# Un_Usb.net
KiCad netlist of a schematic drawn in EAGLE
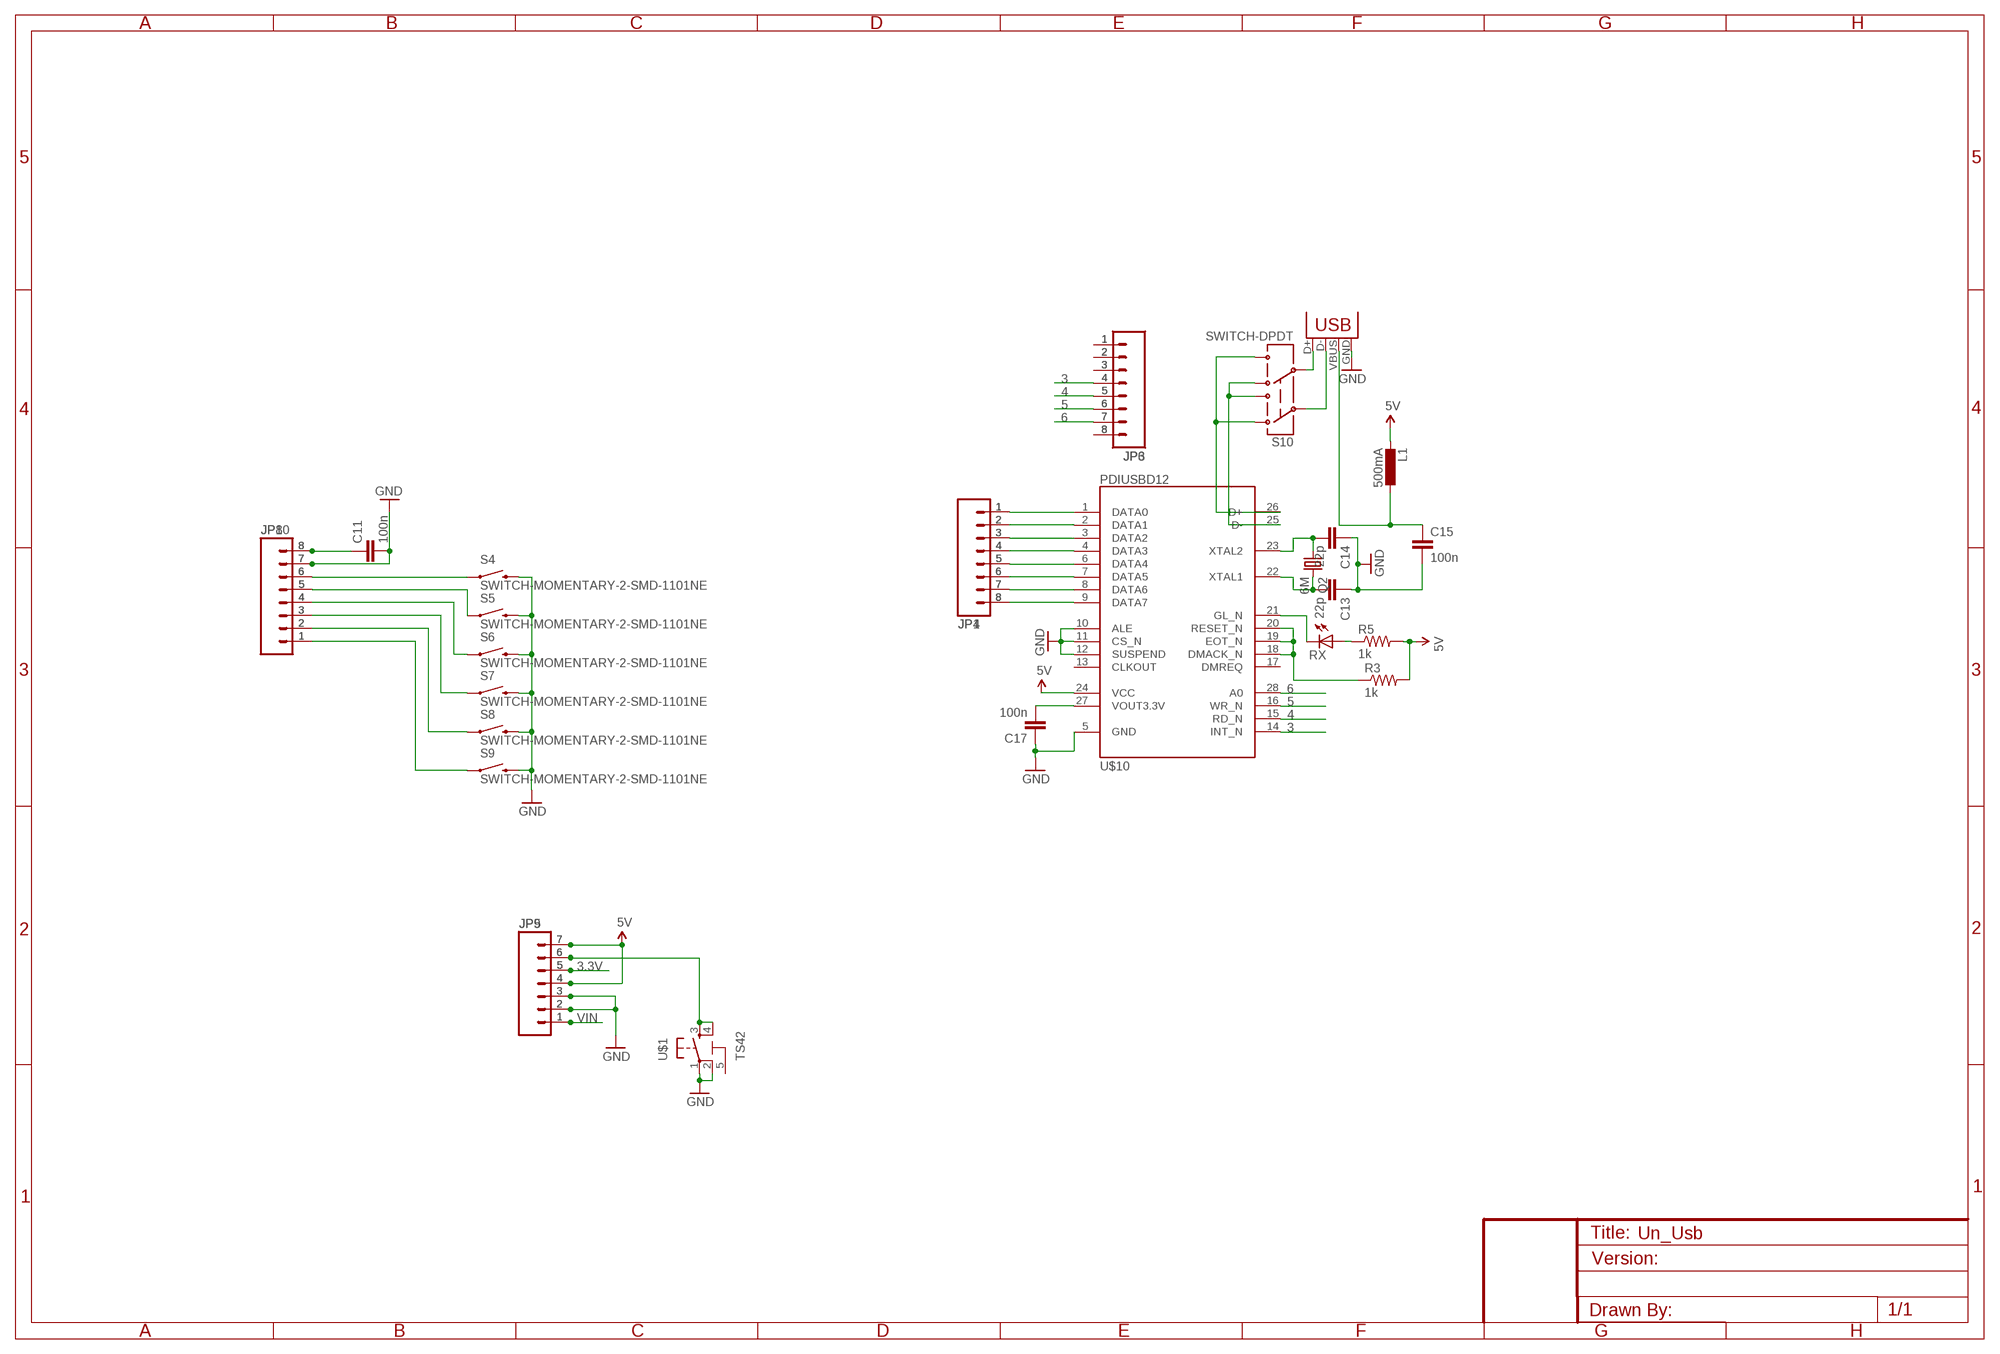
[diagram p0: schematic, sheet 1]

(export (version "E")
  (design (tool "Eeschema 10.0.6"))
  (components
    (comp (ref "C11")
      (value "100n")
      (footprint "eagle-import:0603-CAP")
      (libsource (lib "eagle-import") (part "CAP0603-CAP"))
    )
    (comp (ref "C13")
      (value "22p")
      (footprint "eagle-import:0805")
      (libsource (lib "eagle-import") (part "CAP0805"))
    )
    (comp (ref "C14")
      (value "22p")
      (footprint "eagle-import:0805")
      (libsource (lib "eagle-import") (part "CAP0805"))
    )
    (comp (ref "C15")
      (value "100n")
      (footprint "eagle-import:0603-CAP")
      (libsource (lib "eagle-import") (part "CAP0603-CAP"))
    )
    (comp (ref "C17")
      (value "100n")
      (footprint "eagle-import:0603-CAP")
      (libsource (lib "eagle-import") (part "CAP0603-CAP"))
    )
    (comp (ref "JP1")
      (value "M081X08")
      (footprint "eagle-import:1X08")
      (libsource (lib "eagle-import") (part "M081X08"))
    )
    (comp (ref "JP3")
      (value "M08")
      (footprint "eagle-import:1X08")
      (libsource (lib "eagle-import") (part "M08"))
    )
    (comp (ref "JP4")
      (value "M081X08")
      (footprint "eagle-import:1X08")
      (libsource (lib "eagle-import") (part "M081X08"))
    )
    (comp (ref "JP5")
      (value "M07")
      (footprint "eagle-import:1X07")
      (libsource (lib "eagle-import") (part "M07"))
    )
    (comp (ref "JP6")
      (value "M08")
      (footprint "eagle-import:1X08")
      (libsource (lib "eagle-import") (part "M08"))
    )
    (comp (ref "JP8")
      (value "M08")
      (footprint "eagle-import:1X08")
      (libsource (lib "eagle-import") (part "M08"))
    )
    (comp (ref "JP9")
      (value "M07")
      (footprint "eagle-import:1X07")
      (libsource (lib "eagle-import") (part "M07"))
    )
    (comp (ref "JP10")
      (value "M08")
      (footprint "eagle-import:1X08")
      (libsource (lib "eagle-import") (part "M08"))
    )
    (comp (ref "L1")
      (value "500mA")
      (footprint "eagle-import:L1812")
      (libsource (lib "eagle-import") (part "L-EUL1812"))
    )
    (comp (ref "Q2")
      (value "6M")
      (footprint "eagle-import:HC49US")
      (libsource (lib "eagle-import") (part "CRYSTALHC49US"))
    )
    (comp (ref "R3")
      (value "1k")
      (footprint "eagle-import:0805")
      (libsource (lib "eagle-import") (part "RESISTOR0805-RES"))
    )
    (comp (ref "R5")
      (value "1k")
      (footprint "eagle-import:0805")
      (libsource (lib "eagle-import") (part "RESISTOR0805-RES"))
    )
    (comp (ref "RX")
      (value "LED0805")
      (footprint "eagle-import:LED-0805")
      (libsource (lib "eagle-import") (part "LED0805"))
    )
    (comp (ref "S4")
      (value "SWITCH-MOMENTARY-2-SMD-1101NE")
      (footprint "eagle-import:TACTILE-SWITCH-1101NE")
      (libsource (lib "eagle-import") (part "SWITCH-MOMENTARY-2-SMD-1101NE"))
    )
    (comp (ref "S5")
      (value "SWITCH-MOMENTARY-2-SMD-1101NE")
      (footprint "eagle-import:TACTILE-SWITCH-1101NE")
      (libsource (lib "eagle-import") (part "SWITCH-MOMENTARY-2-SMD-1101NE"))
    )
    (comp (ref "S6")
      (value "SWITCH-MOMENTARY-2-SMD-1101NE")
      (footprint "eagle-import:TACTILE-SWITCH-1101NE")
      (libsource (lib "eagle-import") (part "SWITCH-MOMENTARY-2-SMD-1101NE"))
    )
    (comp (ref "S7")
      (value "SWITCH-MOMENTARY-2-SMD-1101NE")
      (footprint "eagle-import:TACTILE-SWITCH-1101NE")
      (libsource (lib "eagle-import") (part "SWITCH-MOMENTARY-2-SMD-1101NE"))
    )
    (comp (ref "S8")
      (value "SWITCH-MOMENTARY-2-SMD-1101NE")
      (footprint "eagle-import:TACTILE-SWITCH-1101NE")
      (libsource (lib "eagle-import") (part "SWITCH-MOMENTARY-2-SMD-1101NE"))
    )
    (comp (ref "S9")
      (value "SWITCH-MOMENTARY-2-SMD-1101NE")
      (footprint "eagle-import:TACTILE-SWITCH-1101NE")
      (libsource (lib "eagle-import") (part "SWITCH-MOMENTARY-2-SMD-1101NE"))
    )
    (comp (ref "S10")
      (value "SWITCH-DPDT")
      (footprint "eagle-import:SWITCH-P2")
      (libsource (lib "eagle-import") (part "SWITCH-DPDT"))
    )
    (comp (ref "U$1")
      (value "TS42")
      (footprint "eagle-import:TS42")
      (libsource (lib "eagle-import") (part "TS42"))
    )
    (comp (ref "U$10")
      (value "PDIUSBD12")
      (footprint "eagle-import:TSSOP28")
      (libsource (lib "eagle-import") (part "PDIUSBD12"))
    )
    (comp (ref "X2")
      (value "USB")
      (footprint "eagle-import:USB-A-M")
      (libsource (lib "eagle-import") (part "USB"))
    )
  )
  (nets
    (net (code "1") (name "/3") (class "Default")
      (node (ref "JP3") (pin "4") (pinfunction "4_4") (pintype "passive"))
      (node (ref "JP6") (pin "4") (pinfunction "4_4") (pintype "passive"))
      (node (ref "U$10") (pin "14") (pinfunction "INT_N_14") (pintype "bidirectional"))
    )
    (net (code "2") (name "/3.3V") (class "Default")
      (node (ref "JP5") (pin "5") (pinfunction "5_5") (pintype "passive"))
      (node (ref "JP9") (pin "5") (pinfunction "5_5") (pintype "passive"))
    )
    (net (code "3") (name "/4") (class "Default")
      (node (ref "JP3") (pin "5") (pinfunction "5_5") (pintype "passive"))
      (node (ref "JP6") (pin "5") (pinfunction "5_5") (pintype "passive"))
      (node (ref "U$10") (pin "15") (pinfunction "RD_N_15") (pintype "bidirectional"))
    )
    (net (code "4") (name "/5") (class "Default")
      (node (ref "JP3") (pin "6") (pinfunction "6_6") (pintype "passive"))
      (node (ref "JP6") (pin "6") (pinfunction "6_6") (pintype "passive"))
      (node (ref "U$10") (pin "16") (pinfunction "WR_N_16") (pintype "bidirectional"))
    )
    (net (code "5") (name "/6") (class "Default")
      (node (ref "JP3") (pin "7") (pinfunction "7_7") (pintype "passive"))
      (node (ref "JP6") (pin "7") (pinfunction "7_7") (pintype "passive"))
      (node (ref "U$10") (pin "28") (pinfunction "A0_28") (pintype "bidirectional"))
    )
    (net (code "6") (name "/VIN") (class "Default")
      (node (ref "JP5") (pin "1") (pinfunction "1_1") (pintype "passive"))
      (node (ref "JP9") (pin "1") (pinfunction "1_1") (pintype "passive"))
    )
    (net (code "7") (name "5V") (class "Default")
      (node (ref "JP5") (pin "4") (pinfunction "4_4") (pintype "passive"))
      (node (ref "JP5") (pin "7") (pinfunction "7_7") (pintype "passive"))
      (node (ref "JP9") (pin "4") (pinfunction "4_4") (pintype "passive"))
      (node (ref "JP9") (pin "7") (pinfunction "7_7") (pintype "passive"))
      (node (ref "L1") (pin "2") (pinfunction "2_2") (pintype "passive"))
      (node (ref "R3") (pin "2") (pinfunction "2_2") (pintype "passive"))
      (node (ref "R5") (pin "2") (pinfunction "2_2") (pintype "passive"))
      (node (ref "U$10") (pin "24") (pinfunction "VCC_24") (pintype "bidirectional"))
    )
    (net (code "8") (name "GND") (class "Default")
      (node (ref "C11") (pin "2") (pinfunction "2_2") (pintype "passive"))
      (node (ref "C13") (pin "1") (pinfunction "1_1") (pintype "passive"))
      (node (ref "C14") (pin "1") (pinfunction "1_1") (pintype "passive"))
      (node (ref "C15") (pin "2") (pinfunction "2_2") (pintype "passive"))
      (node (ref "C17") (pin "1") (pinfunction "1_1") (pintype "passive"))
      (node (ref "JP10") (pin "7") (pinfunction "7_7") (pintype "passive"))
      (node (ref "JP5") (pin "2") (pinfunction "2_2") (pintype "passive"))
      (node (ref "JP5") (pin "3") (pinfunction "3_3") (pintype "passive"))
      (node (ref "JP8") (pin "7") (pinfunction "7_7") (pintype "passive"))
      (node (ref "JP9") (pin "2") (pinfunction "2_2") (pintype "passive"))
      (node (ref "JP9") (pin "3") (pinfunction "3_3") (pintype "passive"))
      (node (ref "S4") (pin "P$2") (pinfunction "2_P$2") (pintype "passive"))
      (node (ref "S5") (pin "P$2") (pinfunction "2_P$2") (pintype "passive"))
      (node (ref "S6") (pin "P$2") (pinfunction "2_P$2") (pintype "passive"))
      (node (ref "S7") (pin "P$2") (pinfunction "2_P$2") (pintype "passive"))
      (node (ref "S8") (pin "P$2") (pinfunction "2_P$2") (pintype "passive"))
      (node (ref "S9") (pin "P$2") (pinfunction "2_P$2") (pintype "passive"))
      (node (ref "U$1") (pin "1") (pinfunction "1_1") (pintype "passive"))
      (node (ref "U$1") (pin "2") (pinfunction "2_2") (pintype "passive"))
      (node (ref "U$10") (pin "10") (pinfunction "ALE_10") (pintype "bidirectional"))
      (node (ref "U$10") (pin "11") (pinfunction "CS_N_11") (pintype "bidirectional"))
      (node (ref "U$10") (pin "12") (pinfunction "SUSPEND_12") (pintype "bidirectional"))
      (node (ref "U$10") (pin "5") (pinfunction "GND_5") (pintype "bidirectional"))
      (node (ref "X2") (pin "GND") (pinfunction "GND_GND") (pintype "bidirectional"))
    )
    (net (code "9") (name "Net-(C11-Pad1)") (class "Default")
      (node (ref "C11") (pin "1") (pinfunction "1_1") (pintype "passive"))
      (node (ref "JP10") (pin "8") (pinfunction "8_8") (pintype "passive"))
      (node (ref "JP8") (pin "8") (pinfunction "8_8") (pintype "passive"))
    )
    (net (code "10") (name "Net-(C15-Pad1)") (class "Default")
      (node (ref "C15") (pin "1") (pinfunction "1_1") (pintype "passive"))
      (node (ref "L1") (pin "1") (pinfunction "1_1") (pintype "passive"))
      (node (ref "X2") (pin "VBUS") (pinfunction "VBUS_VBUS") (pintype "bidirectional"))
    )
    (net (code "11") (name "Net-(JP3-Pad1)") (class "Default")
      (node (ref "JP3") (pin "1") (pinfunction "1_1") (pintype "passive"))
      (node (ref "JP6") (pin "1") (pinfunction "1_1") (pintype "passive"))
    )
    (net (code "12") (name "Net-(JP3-Pad2)") (class "Default")
      (node (ref "JP3") (pin "2") (pinfunction "2_2") (pintype "passive"))
      (node (ref "JP6") (pin "2") (pinfunction "2_2") (pintype "passive"))
    )
    (net (code "13") (name "Net-(JP3-Pad3)") (class "Default")
      (node (ref "JP3") (pin "3") (pinfunction "3_3") (pintype "passive"))
      (node (ref "JP6") (pin "3") (pinfunction "3_3") (pintype "passive"))
    )
    (net (code "14") (name "Net-(JP3-Pad8)") (class "Default")
      (node (ref "JP3") (pin "8") (pinfunction "8_8") (pintype "passive"))
      (node (ref "JP6") (pin "8") (pinfunction "8_8") (pintype "passive"))
    )
    (net (code "15") (name "Net-(JP5-Pad6)") (class "Default")
      (node (ref "JP5") (pin "6") (pinfunction "6_6") (pintype "passive"))
      (node (ref "JP9") (pin "6") (pinfunction "6_6") (pintype "passive"))
      (node (ref "U$1") (pin "3") (pinfunction "3_3") (pintype "passive"))
      (node (ref "U$1") (pin "4") (pinfunction "4_4") (pintype "passive"))
    )
    (net (code "16") (name "Net-(RX-A)") (class "Default")
      (node (ref "R5") (pin "1") (pinfunction "1_1") (pintype "passive"))
      (node (ref "RX") (pin "1") (pinfunction "A_1") (pintype "passive"))
    )
    (net (code "17") (name "Net-(RX-C)") (class "Default")
      (node (ref "RX") (pin "2") (pinfunction "C_2") (pintype "passive"))
      (node (ref "U$10") (pin "21") (pinfunction "GL_N_21") (pintype "bidirectional"))
    )
    (net (code "18") (name "Net-(S4-1)") (class "Default")
      (node (ref "JP10") (pin "6") (pinfunction "6_6") (pintype "passive"))
      (node (ref "JP8") (pin "6") (pinfunction "6_6") (pintype "passive"))
      (node (ref "S4") (pin "P$1") (pinfunction "1_P$1") (pintype "passive"))
    )
    (net (code "19") (name "Net-(S5-1)") (class "Default")
      (node (ref "JP10") (pin "5") (pinfunction "5_5") (pintype "passive"))
      (node (ref "JP8") (pin "5") (pinfunction "5_5") (pintype "passive"))
      (node (ref "S5") (pin "P$1") (pinfunction "1_P$1") (pintype "passive"))
    )
    (net (code "20") (name "Net-(S6-1)") (class "Default")
      (node (ref "JP10") (pin "4") (pinfunction "4_4") (pintype "passive"))
      (node (ref "JP8") (pin "4") (pinfunction "4_4") (pintype "passive"))
      (node (ref "S6") (pin "P$1") (pinfunction "1_P$1") (pintype "passive"))
    )
    (net (code "21") (name "Net-(S7-1)") (class "Default")
      (node (ref "JP10") (pin "3") (pinfunction "3_3") (pintype "passive"))
      (node (ref "JP8") (pin "3") (pinfunction "3_3") (pintype "passive"))
      (node (ref "S7") (pin "P$1") (pinfunction "1_P$1") (pintype "passive"))
    )
    (net (code "22") (name "Net-(S8-1)") (class "Default")
      (node (ref "JP10") (pin "2") (pinfunction "2_2") (pintype "passive"))
      (node (ref "JP8") (pin "2") (pinfunction "2_2") (pintype "passive"))
      (node (ref "S8") (pin "P$1") (pinfunction "1_P$1") (pintype "passive"))
    )
    (net (code "23") (name "Net-(S9-1)") (class "Default")
      (node (ref "JP10") (pin "1") (pinfunction "1_1") (pintype "passive"))
      (node (ref "JP8") (pin "1") (pinfunction "1_1") (pintype "passive"))
      (node (ref "S9") (pin "P$1") (pinfunction "1_P$1") (pintype "passive"))
    )
    (net (code "24") (name "Net-(S10-Pad2)") (class "Default")
      (node (ref "S10") (pin "2") (pinfunction "2_2") (pintype "bidirectional"))
      (node (ref "X2") (pin "D-") (pinfunction "D-_D-") (pintype "bidirectional"))
    )
    (net (code "25") (name "Net-(S10-Pad5)") (class "Default")
      (node (ref "S10") (pin "5") (pinfunction "5_5") (pintype "bidirectional"))
      (node (ref "X2") (pin "D+") (pinfunction "D+_D+") (pintype "bidirectional"))
    )
    (net (code "26") (name "Net-(U$10-D+)") (class "Default")
      (node (ref "S10") (pin "1") (pinfunction "1_1") (pintype "bidirectional"))
      (node (ref "S10") (pin "6") (pinfunction "6_6") (pintype "bidirectional"))
      (node (ref "U$10") (pin "26") (pinfunction "D+_26") (pintype "bidirectional"))
    )
    (net (code "27") (name "Net-(U$10-D-)") (class "Default")
      (node (ref "S10") (pin "3") (pinfunction "3_3") (pintype "bidirectional"))
      (node (ref "S10") (pin "4") (pinfunction "4_4") (pintype "bidirectional"))
      (node (ref "U$10") (pin "25") (pinfunction "D-_25") (pintype "bidirectional"))
    )
    (net (code "28") (name "Net-(U$10-DATA0)") (class "Default")
      (node (ref "JP1") (pin "1") (pinfunction "1_1") (pintype "passive"))
      (node (ref "JP4") (pin "1") (pinfunction "1_1") (pintype "passive"))
      (node (ref "U$10") (pin "1") (pinfunction "DATA0_1") (pintype "bidirectional"))
    )
    (net (code "29") (name "Net-(U$10-DATA1)") (class "Default")
      (node (ref "JP1") (pin "2") (pinfunction "2_2") (pintype "passive"))
      (node (ref "JP4") (pin "2") (pinfunction "2_2") (pintype "passive"))
      (node (ref "U$10") (pin "2") (pinfunction "DATA1_2") (pintype "bidirectional"))
    )
    (net (code "30") (name "Net-(U$10-DATA2)") (class "Default")
      (node (ref "JP1") (pin "3") (pinfunction "3_3") (pintype "passive"))
      (node (ref "JP4") (pin "3") (pinfunction "3_3") (pintype "passive"))
      (node (ref "U$10") (pin "3") (pinfunction "DATA2_3") (pintype "bidirectional"))
    )
    (net (code "31") (name "Net-(U$10-DATA3)") (class "Default")
      (node (ref "JP1") (pin "4") (pinfunction "4_4") (pintype "passive"))
      (node (ref "JP4") (pin "4") (pinfunction "4_4") (pintype "passive"))
      (node (ref "U$10") (pin "4") (pinfunction "DATA3_4") (pintype "bidirectional"))
    )
    (net (code "32") (name "Net-(U$10-DATA4)") (class "Default")
      (node (ref "JP1") (pin "5") (pinfunction "5_5") (pintype "passive"))
      (node (ref "JP4") (pin "5") (pinfunction "5_5") (pintype "passive"))
      (node (ref "U$10") (pin "6") (pinfunction "DATA4_6") (pintype "bidirectional"))
    )
    (net (code "33") (name "Net-(U$10-DATA5)") (class "Default")
      (node (ref "JP1") (pin "6") (pinfunction "6_6") (pintype "passive"))
      (node (ref "JP4") (pin "6") (pinfunction "6_6") (pintype "passive"))
      (node (ref "U$10") (pin "7") (pinfunction "DATA5_7") (pintype "bidirectional"))
    )
    (net (code "34") (name "Net-(U$10-DATA6)") (class "Default")
      (node (ref "JP1") (pin "7") (pinfunction "7_7") (pintype "passive"))
      (node (ref "JP4") (pin "7") (pinfunction "7_7") (pintype "passive"))
      (node (ref "U$10") (pin "8") (pinfunction "DATA6_8") (pintype "bidirectional"))
    )
    (net (code "35") (name "Net-(U$10-DATA7)") (class "Default")
      (node (ref "JP1") (pin "8") (pinfunction "8_8") (pintype "passive"))
      (node (ref "JP4") (pin "8") (pinfunction "8_8") (pintype "passive"))
      (node (ref "U$10") (pin "9") (pinfunction "DATA7_9") (pintype "bidirectional"))
    )
    (net (code "36") (name "Net-(U$10-DMACK_N)") (class "Default")
      (node (ref "R3") (pin "1") (pinfunction "1_1") (pintype "passive"))
      (node (ref "U$10") (pin "18") (pinfunction "DMACK_N_18") (pintype "bidirectional"))
      (node (ref "U$10") (pin "19") (pinfunction "EOT_N_19") (pintype "bidirectional"))
      (node (ref "U$10") (pin "20") (pinfunction "RESET_N_20") (pintype "bidirectional"))
    )
    (net (code "37") (name "Net-(U$10-VOUT3.3V)") (class "Default")
      (node (ref "C17") (pin "2") (pinfunction "2_2") (pintype "passive"))
      (node (ref "U$10") (pin "27") (pinfunction "VOUT3.3V_27") (pintype "bidirectional"))
    )
    (net (code "38") (name "Net-(U$10-XTAL1)") (class "Default")
      (node (ref "C13") (pin "2") (pinfunction "2_2") (pintype "passive"))
      (node (ref "Q2") (pin "2") (pinfunction "2_2") (pintype "passive"))
      (node (ref "U$10") (pin "22") (pinfunction "XTAL1_22") (pintype "bidirectional"))
    )
    (net (code "39") (name "Net-(U$10-XTAL2)") (class "Default")
      (node (ref "C14") (pin "2") (pinfunction "2_2") (pintype "passive"))
      (node (ref "Q2") (pin "1") (pinfunction "1_1") (pintype "passive"))
      (node (ref "U$10") (pin "23") (pinfunction "XTAL2_23") (pintype "bidirectional"))
    )
    (net (code "40") (name "unconnected-(U$1-Pad5)") (class "Default")
      (node (ref "U$1") (pin "5") (pinfunction "5_5") (pintype "passive"))
    )
    (net (code "41") (name "unconnected-(U$10-CLKOUT-Pad13)") (class "Default")
      (node (ref "U$10") (pin "13") (pinfunction "CLKOUT_13") (pintype "bidirectional"))
    )
    (net (code "42") (name "unconnected-(U$10-DMREQ-Pad17)") (class "Default")
      (node (ref "U$10") (pin "17") (pinfunction "DMREQ_17") (pintype "bidirectional"))
    )
  )
)
